# 05_RFFE.net
KiCad netlist of a schematic drawn in Altium Designer
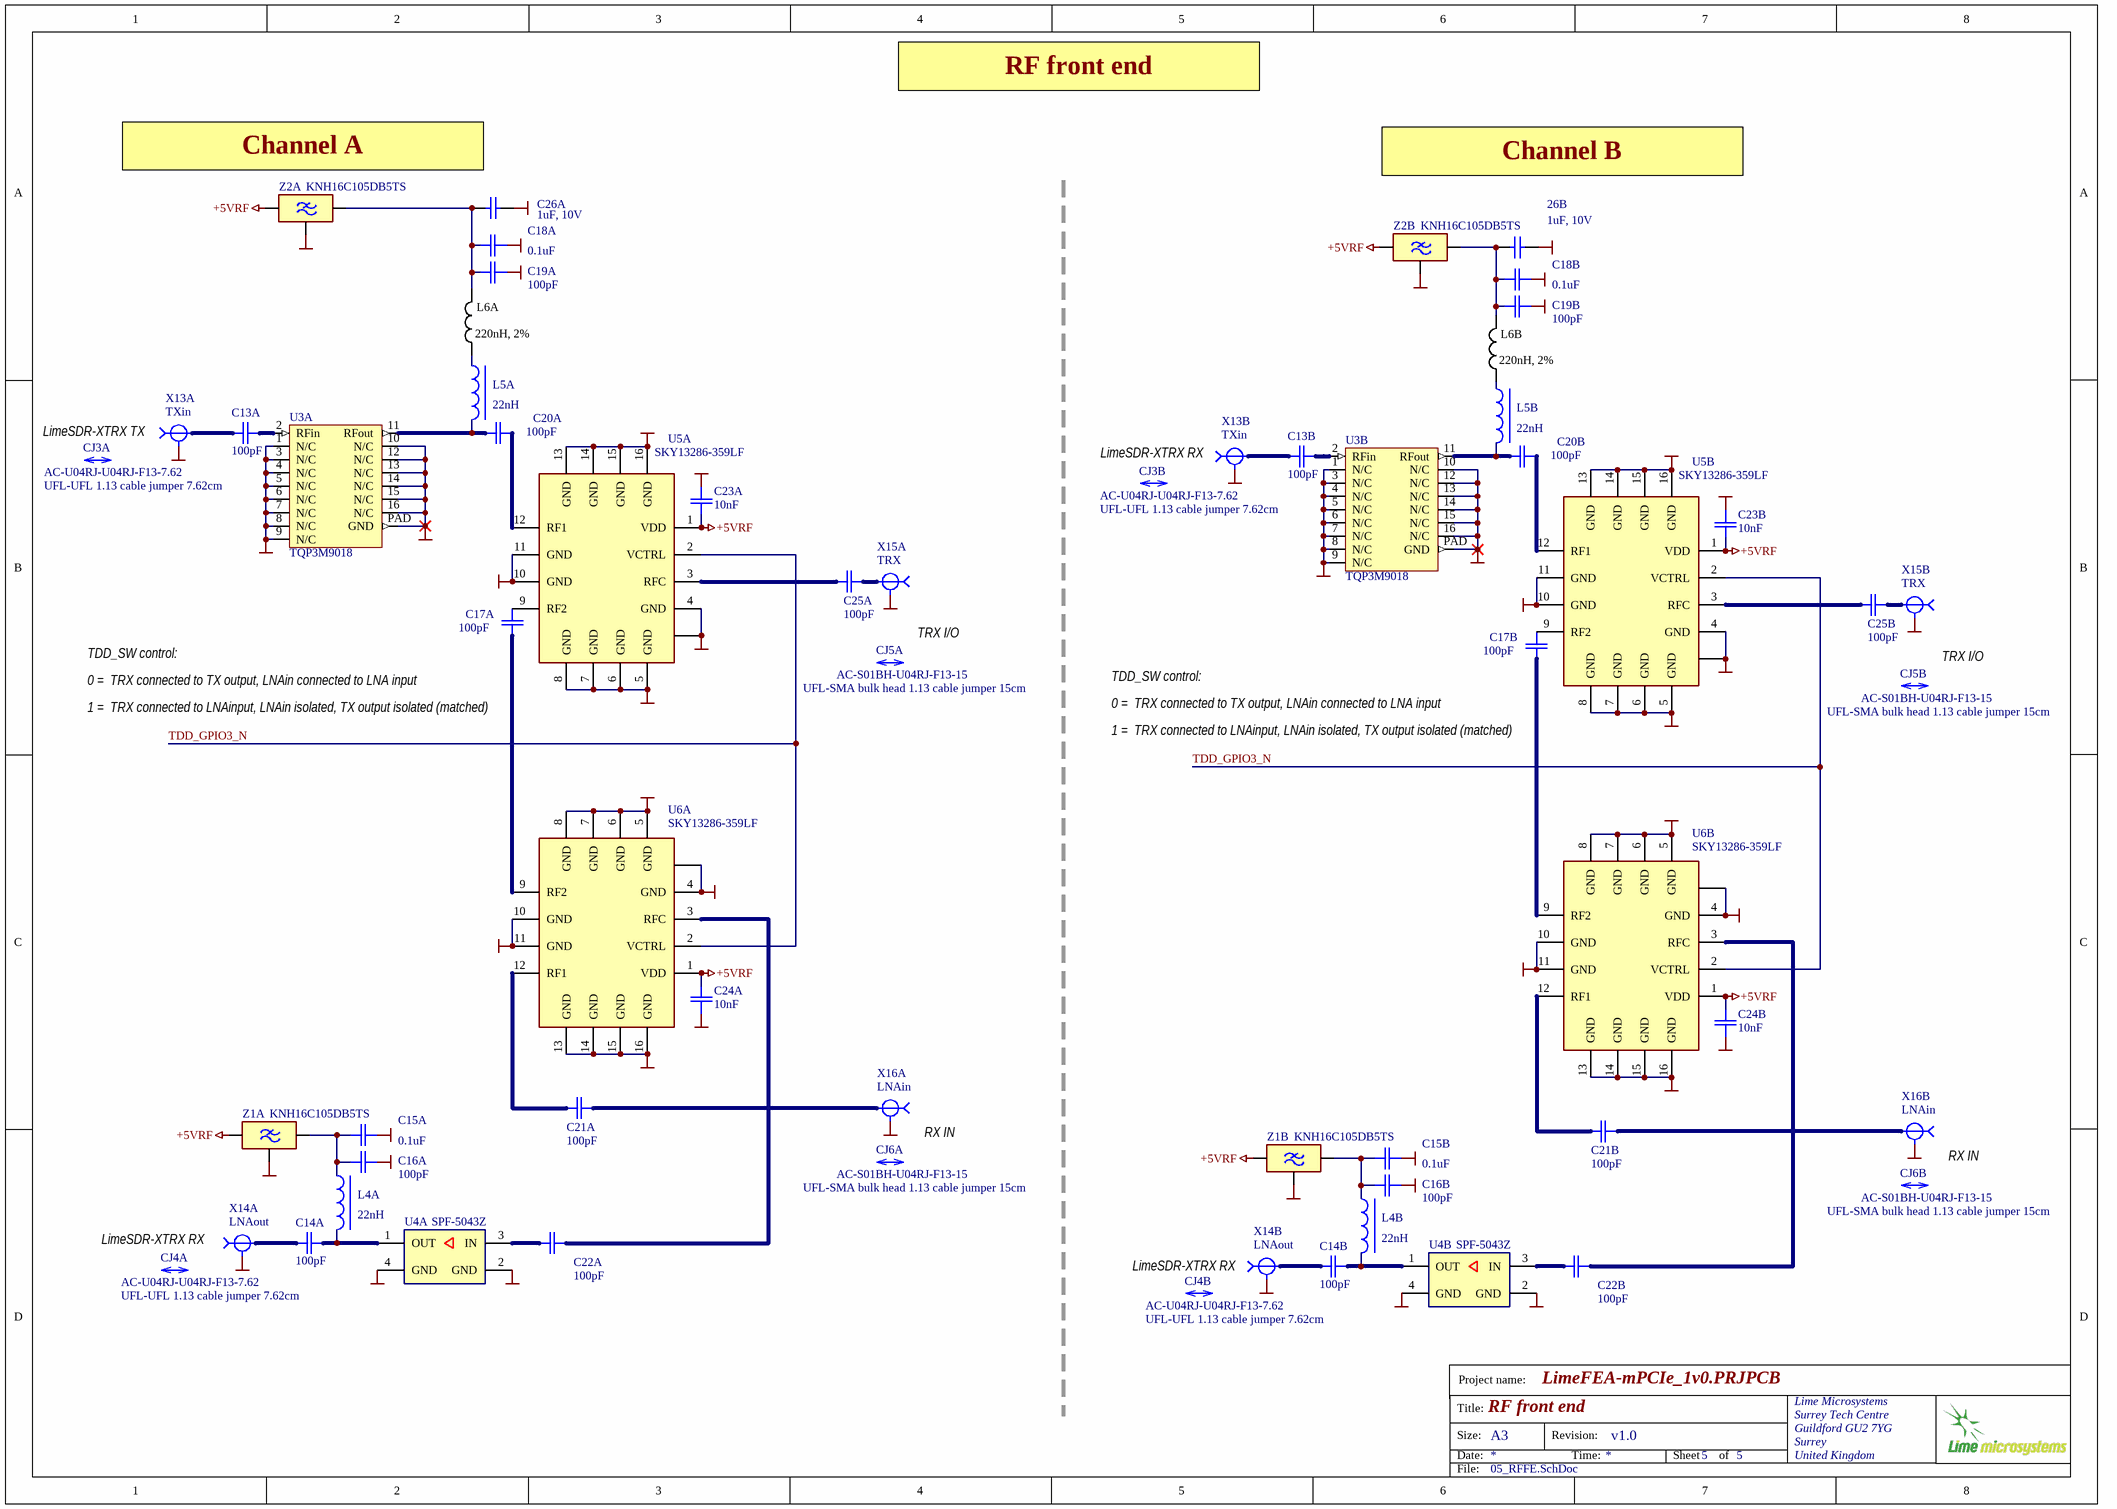
[diagram p0: 05_RFFE.SchDoc]

(export (version "E")
  (design (tool "Eeschema 10.0.6"))
  (components
    (comp (ref "26B")
      (value "1uF, 10V")
      (footprint "CAP0402")
      (description "CAP CER 1UF 10V X5R 0402")
      (fields (field (name "MANUFACTURER") "Yageo") (field (name "TOLERANCE") "±20%"))
      (libsource (lib "LimeMicroAltiumLib_schLib") (part "Cap_0402"))
    )
    (comp (ref "C13A")
      (value "100pF")
      (footprint "C0603-PHILLIPS")
      (description "Capacitor")
      (fields (field (name "MANUFACTURER") "MURATA") (field (name "TOLERANCE") "20%"))
      (libsource (lib "altium-import") (part "root_1_C0603_"))
    )
    (comp (ref "C13B")
      (value "100pF")
      (footprint "C0603-PHILLIPS")
      (description "Capacitor")
      (fields (field (name "MANUFACTURER") "MURATA") (field (name "TOLERANCE") "20%"))
      (libsource (lib "altium-import") (part "root_1_C0603_"))
    )
    (comp (ref "C14A")
      (value "100pF")
      (footprint "C0603-PHILLIPS")
      (description "Capacitor")
      (fields (field (name "MANUFACTURER") "MURATA") (field (name "TOLERANCE") "20%"))
      (libsource (lib "altium-import") (part "root_1_C0603_"))
    )
    (comp (ref "C14B")
      (value "100pF")
      (footprint "C0603-PHILLIPS")
      (description "Capacitor")
      (fields (field (name "MANUFACTURER") "MURATA") (field (name "TOLERANCE") "20%"))
      (libsource (lib "altium-import") (part "root_1_C0603_"))
    )
    (comp (ref "C15A")
      (value "0.1uF")
      (footprint "C0603-PHILLIPS")
      (description "Capacitor")
      (fields (field (name "MANUFACTURER") "MURATA") (field (name "TOLERANCE") "20%"))
      (libsource (lib "altium-import") (part "root_3_mirrored_C0603_"))
    )
    (comp (ref "C15B")
      (value "0.1uF")
      (footprint "C0603-PHILLIPS")
      (description "Capacitor")
      (fields (field (name "MANUFACTURER") "MURATA") (field (name "TOLERANCE") "20%"))
      (libsource (lib "altium-import") (part "root_3_mirrored_C0603_"))
    )
    (comp (ref "C16A")
      (value "100pF")
      (footprint "C0603-PHILLIPS")
      (description "Capacitor")
      (fields (field (name "MANUFACTURER") "MURATA") (field (name "TOLERANCE") "20%"))
      (libsource (lib "altium-import") (part "root_1_C0603_"))
    )
    (comp (ref "C16B")
      (value "100pF")
      (footprint "C0603-PHILLIPS")
      (description "Capacitor")
      (fields (field (name "MANUFACTURER") "MURATA") (field (name "TOLERANCE") "20%"))
      (libsource (lib "altium-import") (part "root_1_C0603_"))
    )
    (comp (ref "C17A")
      (value "100pF")
      (footprint "C0603-PHILLIPS")
      (description "Capacitor")
      (fields (field (name "MANUFACTURER") "MURATA") (field (name "TOLERANCE") "20%"))
      (libsource (lib "altium-import") (part "root_2_C0603_"))
    )
    (comp (ref "C17B")
      (value "100pF")
      (footprint "C0603-PHILLIPS")
      (description "Capacitor")
      (fields (field (name "MANUFACTURER") "MURATA") (field (name "TOLERANCE") "20%"))
      (libsource (lib "altium-import") (part "root_2_C0603_"))
    )
    (comp (ref "C18A")
      (value "0.1uF")
      (footprint "C0603-PHILLIPS")
      (description "Capacitor")
      (fields (field (name "MANUFACTURER") "MURATA") (field (name "TOLERANCE") "20%"))
      (libsource (lib "altium-import") (part "root_3_mirrored_C0603_"))
    )
    (comp (ref "C18B")
      (value "0.1uF")
      (footprint "C0603-PHILLIPS")
      (description "Capacitor")
      (fields (field (name "MANUFACTURER") "MURATA") (field (name "TOLERANCE") "20%"))
      (libsource (lib "altium-import") (part "root_3_mirrored_C0603_"))
    )
    (comp (ref "C19A")
      (value "100pF")
      (footprint "C0603-PHILLIPS")
      (description "Capacitor")
      (fields (field (name "MANUFACTURER") "MURATA") (field (name "TOLERANCE") "20%"))
      (libsource (lib "altium-import") (part "root_1_C0603_"))
    )
    (comp (ref "C19B")
      (value "100pF")
      (footprint "C0603-PHILLIPS")
      (description "Capacitor")
      (fields (field (name "MANUFACTURER") "MURATA") (field (name "TOLERANCE") "20%"))
      (libsource (lib "altium-import") (part "root_1_C0603_"))
    )
    (comp (ref "C20A")
      (value "100pF")
      (footprint "C0603-PHILLIPS")
      (description "Capacitor")
      (fields (field (name "MANUFACTURER") "MURATA") (field (name "TOLERANCE") "20%"))
      (libsource (lib "altium-import") (part "root_1_C0603_"))
    )
    (comp (ref "C20B")
      (value "100pF")
      (footprint "C0603-PHILLIPS")
      (description "Capacitor")
      (fields (field (name "MANUFACTURER") "MURATA") (field (name "TOLERANCE") "20%"))
      (libsource (lib "altium-import") (part "root_1_C0603_"))
    )
    (comp (ref "C21A")
      (value "100pF")
      (footprint "C0603-PHILLIPS")
      (description "Capacitor")
      (fields (field (name "MANUFACTURER") "MURATA") (field (name "TOLERANCE") "20%"))
      (libsource (lib "altium-import") (part "root_1_C0603_"))
    )
    (comp (ref "C21B")
      (value "100pF")
      (footprint "C0603-PHILLIPS")
      (description "Capacitor")
      (fields (field (name "MANUFACTURER") "MURATA") (field (name "TOLERANCE") "20%"))
      (libsource (lib "altium-import") (part "root_1_C0603_"))
    )
    (comp (ref "C22A")
      (value "100pF")
      (footprint "C0603-PHILLIPS")
      (description "Capacitor")
      (fields (field (name "MANUFACTURER") "MURATA") (field (name "TOLERANCE") "20%"))
      (libsource (lib "altium-import") (part "root_1_C0603_"))
    )
    (comp (ref "C22B")
      (value "100pF")
      (footprint "C0603-PHILLIPS")
      (description "Capacitor")
      (fields (field (name "MANUFACTURER") "MURATA") (field (name "TOLERANCE") "20%"))
      (libsource (lib "altium-import") (part "root_1_C0603_"))
    )
    (comp (ref "C23A")
      (value "10nF")
      (footprint "C0603-PHILLIPS")
      (description "Capacitor")
      (fields (field (name "MANUFACTURER") "MURATA") (field (name "TOLERANCE") "20%"))
      (libsource (lib "altium-import") (part "root_2_C0603_"))
    )
    (comp (ref "C23B")
      (value "10nF")
      (footprint "C0603-PHILLIPS")
      (description "Capacitor")
      (fields (field (name "MANUFACTURER") "MURATA") (field (name "TOLERANCE") "20%"))
      (libsource (lib "altium-import") (part "root_2_C0603_"))
    )
    (comp (ref "C24A")
      (value "10nF")
      (footprint "C0603-PHILLIPS")
      (description "Capacitor")
      (fields (field (name "MANUFACTURER") "MURATA") (field (name "TOLERANCE") "20%"))
      (libsource (lib "altium-import") (part "root_0_C0603_"))
    )
    (comp (ref "C24B")
      (value "10nF")
      (footprint "C0603-PHILLIPS")
      (description "Capacitor")
      (fields (field (name "MANUFACTURER") "MURATA") (field (name "TOLERANCE") "20%"))
      (libsource (lib "altium-import") (part "root_0_C0603_"))
    )
    (comp (ref "C25A")
      (value "100pF")
      (footprint "C0603-PHILLIPS")
      (description "Capacitor")
      (fields (field (name "MANUFACTURER") "MURATA") (field (name "TOLERANCE") "20%"))
      (libsource (lib "altium-import") (part "root_1_C0603_"))
    )
    (comp (ref "C25B")
      (value "100pF")
      (footprint "C0603-PHILLIPS")
      (description "Capacitor")
      (fields (field (name "MANUFACTURER") "MURATA") (field (name "TOLERANCE") "20%"))
      (libsource (lib "altium-import") (part "root_1_C0603_"))
    )
    (comp (ref "C26A")
      (value "1uF, 10V")
      (footprint "CAP0402")
      (description "CAP CER 1UF 10V X5R 0402")
      (fields (field (name "MANUFACTURER") "Yageo") (field (name "TOLERANCE") "±20%"))
      (libsource (lib "LimeMicroAltiumLib_schLib") (part "Cap_0402"))
    )
    (comp (ref "CJ3A")
      (value "AC-U04RJ-U04RJ-F13-7.62")
      (description "Cable jumper")
      (fields
        (field (name "MANUFACTURER") "RFSupplier")
        (field (name "MISC") "UFL-UFL 1.13 cable jumper 7.62cm")
      )
      (libsource (lib "LimeFEA-mPCIe_1v0") (part "Mating part"))
    )
    (comp (ref "CJ3B")
      (value "AC-U04RJ-U04RJ-F13-7.62")
      (description "Cable jumper")
      (fields
        (field (name "MANUFACTURER") "RFSupplier")
        (field (name "MISC") "UFL-UFL 1.13 cable jumper 7.62cm")
      )
      (libsource (lib "Andy") (part "Mating part"))
    )
    (comp (ref "CJ4A")
      (value "AC-U04RJ-U04RJ-F13-7.62")
      (description "Cable jumper")
      (fields
        (field (name "MANUFACTURER") "RFSupplier")
        (field (name "MISC") "UFL-UFL 1.13 cable jumper 7.62cm")
      )
      (libsource (lib "LimeFEA-mPCIe_1v0") (part "Mating part"))
    )
    (comp (ref "CJ4B")
      (value "AC-U04RJ-U04RJ-F13-7.62")
      (description "Cable jumper")
      (fields
        (field (name "MANUFACTURER") "RFSupplier")
        (field (name "MISC") "UFL-UFL 1.13 cable jumper 7.62cm")
      )
      (libsource (lib "LimeFEA-mPCIe_1v0") (part "Mating part"))
    )
    (comp (ref "CJ5A")
      (value "AC-S01BH-U04RJ-F13-15")
      (description "Cable jumper")
      (fields
        (field (name "MANUFACTURER") "RFSupplier")
        (field (name "MISC") "UFL-SMA bulk head 1.13 cable jumper 15cm")
      )
      (libsource (lib "Andy") (part "Mating part"))
    )
    (comp (ref "CJ5B")
      (value "AC-S01BH-U04RJ-F13-15")
      (description "Cable jumper")
      (fields
        (field (name "MANUFACTURER") "RFSupplier")
        (field (name "MISC") "UFL-SMA bulk head 1.13 cable jumper 15cm")
      )
      (libsource (lib "LimeFEA-mPCIe_1v0") (part "Mating part"))
    )
    (comp (ref "CJ6A")
      (value "AC-S01BH-U04RJ-F13-15")
      (description "Cable jumper")
      (fields
        (field (name "MANUFACTURER") "RFSupplier")
        (field (name "MISC") "UFL-SMA bulk head 1.13 cable jumper 15cm")
      )
      (libsource (lib "Andy") (part "Mating part"))
    )
    (comp (ref "CJ6B")
      (value "AC-S01BH-U04RJ-F13-15")
      (description "Cable jumper")
      (fields
        (field (name "MANUFACTURER") "RFSupplier")
        (field (name "MISC") "UFL-SMA bulk head 1.13 cable jumper 15cm")
      )
      (libsource (lib "LimeFEA-mPCIe_1v0") (part "Mating part"))
    )
    (comp (ref "L4A")
      (value "22nH")
      (footprint "TF160808-Phillips")
      (description "Coil")
      (fields (field (name "MANUFACTURER") "MuRata"))
      (libsource (lib "LimeFEA-mPCIe_1v0") (part "TF160808"))
    )
    (comp (ref "L4B")
      (value "22nH")
      (footprint "TF160808-Phillips")
      (description "Coil")
      (fields (field (name "MANUFACTURER") "MuRata"))
      (libsource (lib "LimeFEA-mPCIe_1v0") (part "TF160808"))
    )
    (comp (ref "L5A")
      (value "22nH")
      (footprint "TF160808-Phillips")
      (description "Coil")
      (fields (field (name "MANUFACTURER") "MuRata"))
      (libsource (lib "LimeFEA-mPCIe_1v0") (part "TF160808"))
    )
    (comp (ref "L5B")
      (value "22nH")
      (footprint "TF160808-Phillips")
      (description "Coil")
      (fields (field (name "MANUFACTURER") "MuRata"))
      (libsource (lib "LimeFEA-mPCIe_1v0") (part "TF160808"))
    )
    (comp (ref "L6A")
      (value "220nH, 2%")
      (footprint "RES0603")
      (description "Power Inductors - SMD .22 UH 20%")
      (fields (field (name "MANUFACTURER") "TDK"))
      (libsource (lib "LimeMicroAltiumLib_schLib") (part "Inductor"))
    )
    (comp (ref "L6B")
      (value "220nH, 2%")
      (footprint "RES0603")
      (description "Power Inductors - SMD .22 UH 20%")
      (fields (field (name "MANUFACTURER") "TDK"))
      (libsource (lib "LimeMicroAltiumLib_schLib") (part "Inductor"))
    )
    (comp (ref "U3A")
      (value "TQP3M9018")
      (footprint "TQP3M9018_PA_QFN16")
      (description "RF Amplifier .05-4GHz P1dB= 22dB Gain 26.4dB 5Volts")
      (fields (field (name "MANUFACTURER") "Qorvo"))
      (libsource (lib "LimeMicroAltiumLib") (part "TQP3M9018_PA"))
    )
    (comp (ref "U3B")
      (value "TQP3M9018")
      (footprint "TQP3M9018_PA_QFN16")
      (description "RF Amplifier .05-4GHz P1dB= 22dB Gain 26.4dB 5Volts")
      (fields (field (name "MANUFACTURER") "Qorvo"))
      (libsource (lib "LimeMicroAltiumLib") (part "TQP3M9018_PA"))
    )
    (comp (ref "U4A")
      (value "SPF-5043Z")
      (footprint "SOT-343[2X1.25]")
      (description "IC")
      (fields (field (name "MANUFACTURER") "RFMD"))
      (libsource (lib "LimeFEA-mPCIe_1v0") (part "SPF-5043Z"))
    )
    (comp (ref "U4B")
      (value "SPF-5043Z")
      (footprint "SOT-343[2X1.25]")
      (description "IC")
      (fields (field (name "MANUFACTURER") "RFMD"))
      (libsource (lib "LimeFEA-mPCIe_1v0") (part "SPF-5043Z"))
    )
    (comp (ref "U5A")
      (value "SKY13286-359LF")
      (footprint "QFN16(4x4/0.65mm) SQ")
      (description "IC RF SPDT Absorptive Switch")
      (fields (field (name "MANUFACTURER") "Skyworks"))
      (libsource (lib "LimeFEA-mPCIe_1v0") (part "SKY13286-359LF"))
    )
    (comp (ref "U5B")
      (value "SKY13286-359LF")
      (footprint "QFN16(4x4/0.65mm) SQ")
      (description "IC RF SPDT Absorptive Switch")
      (fields (field (name "MANUFACTURER") "Skyworks"))
      (libsource (lib "LimeFEA-mPCIe_1v0") (part "SKY13286-359LF"))
    )
    (comp (ref "U6A")
      (value "SKY13286-359LF")
      (footprint "QFN16(4x4/0.65mm) SQ")
      (description "IC RF SPDT Absorptive Switch")
      (fields (field (name "MANUFACTURER") "Skyworks"))
      (libsource (lib "") (part "SKY13286-359LF_1"))
    )
    (comp (ref "U6B")
      (value "SKY13286-359LF")
      (footprint "QFN16(4x4/0.65mm) SQ")
      (description "IC RF SPDT Absorptive Switch")
      (fields (field (name "MANUFACTURER") "Skyworks"))
      (libsource (lib "") (part "SKY13286-359LF_1"))
    )
    (comp (ref "X13A")
      (value "0734120110")
      (footprint "U_FL")
      (description "Connector (UMCC)")
      (fields (field (name "MANUFACTURER") "Molex") (field (name "MISC") "TXin"))
      (libsource (lib "LimeFEA-mPCIe_1v0") (part "U_FL"))
    )
    (comp (ref "X13B")
      (value "0734120110")
      (footprint "U_FL")
      (description "Connector (UMCC)")
      (fields (field (name "MANUFACTURER") "Molex") (field (name "MISC") "TXin"))
      (libsource (lib "LimeFEA-mPCIe_1v0") (part "U_FL"))
    )
    (comp (ref "X14A")
      (value "0734120110")
      (footprint "U_FL")
      (description "Connector (UMCC)")
      (fields (field (name "MANUFACTURER") "Molex") (field (name "MISC") "LNAout"))
      (libsource (lib "LimeFEA-mPCIe_1v0") (part "U_FL"))
    )
    (comp (ref "X14B")
      (value "0734120110")
      (footprint "U_FL")
      (description "Connector (UMCC)")
      (fields (field (name "MANUFACTURER") "Molex") (field (name "MISC") "LNAout"))
      (libsource (lib "LimeFEA-mPCIe_1v0") (part "U_FL"))
    )
    (comp (ref "X15A")
      (value "0734120110")
      (footprint "U_FL")
      (description "Connector (UMCC)")
      (fields (field (name "MANUFACTURER") "Molex") (field (name "MISC") "TRX"))
      (libsource (lib "LimeFEA-mPCIe_1v0") (part "U_FL"))
    )
    (comp (ref "X15B")
      (value "0734120110")
      (footprint "U_FL")
      (description "Connector (UMCC)")
      (fields (field (name "MANUFACTURER") "Molex") (field (name "MISC") "TRX"))
      (libsource (lib "LimeFEA-mPCIe_1v0") (part "U_FL"))
    )
    (comp (ref "X16A")
      (value "0734120110")
      (footprint "U_FL")
      (description "Connector (UMCC)")
      (fields (field (name "MANUFACTURER") "Molex") (field (name "MISC") "LNAin"))
      (libsource (lib "LimeFEA-mPCIe_1v0") (part "U_FL"))
    )
    (comp (ref "X16B")
      (value "0734120110")
      (footprint "U_FL")
      (description "Connector (UMCC)")
      (fields (field (name "MANUFACTURER") "Molex") (field (name "MISC") "LNAin"))
      (libsource (lib "LimeFEA-mPCIe_1v0") (part "U_FL"))
    )
    (comp (ref "Z1A")
      (value "KNH16C105DB5TS")
      (footprint "KNH16 - DB Serie")
      (description "EMI Filter")
      (fields (field (name "MANUFACTURER") "AVX / Kyocera"))
      (libsource (lib "LimeFEA-mPCIe_1v0") (part "KNH16 Serie"))
    )
    (comp (ref "Z1B")
      (value "KNH16C105DB5TS")
      (footprint "KNH16 - DB Serie")
      (description "EMI Filter")
      (fields (field (name "MANUFACTURER") "AVX / Kyocera"))
      (libsource (lib "LimeFEA-mPCIe_1v0") (part "KNH16 Serie"))
    )
    (comp (ref "Z2A")
      (value "KNH16C105DB5TS")
      (footprint "KNH16 - DB Serie")
      (description "EMI Filter")
      (fields (field (name "MANUFACTURER") "AVX / Kyocera"))
      (libsource (lib "LimeFEA-mPCIe_1v0") (part "KNH16 Serie"))
    )
    (comp (ref "Z2B")
      (value "KNH16C105DB5TS")
      (footprint "KNH16 - DB Serie")
      (description "EMI Filter")
      (fields (field (name "MANUFACTURER") "AVX / Kyocera"))
      (libsource (lib "LimeFEA-mPCIe_1v0") (part "KNH16 Serie"))
    )
  )
  (nets
    (net (code "1") (name "+5VRF") (class "Default")
      (node (ref "C23A") (pin "1") (pinfunction "1_1") (pintype "passive"))
      (node (ref "C23B") (pin "1") (pinfunction "1_1") (pintype "passive"))
      (node (ref "C24A") (pin "1") (pinfunction "1_1") (pintype "passive"))
      (node (ref "C24B") (pin "1") (pinfunction "1_1") (pintype "passive"))
      (node (ref "U5A") (pin "1") (pinfunction "VDD_1") (pintype "passive"))
      (node (ref "U5B") (pin "1") (pinfunction "VDD_1") (pintype "passive"))
      (node (ref "U6A") (pin "1") (pinfunction "VDD_1") (pintype "passive"))
      (node (ref "U6B") (pin "1") (pinfunction "VDD_1") (pintype "passive"))
      (node (ref "Z1A") (pin "1") (pinfunction "1_1") (pintype "passive"))
      (node (ref "Z1B") (pin "1") (pinfunction "1_1") (pintype "passive"))
      (node (ref "Z2A") (pin "1") (pinfunction "1_1") (pintype "passive"))
      (node (ref "Z2B") (pin "1") (pinfunction "1_1") (pintype "passive"))
    )
    (net (code "2") (name "/TDD_GPIO3_N") (class "Default")
      (node (ref "U5A") (pin "2") (pinfunction "VCTRL_2") (pintype "passive"))
      (node (ref "U5B") (pin "2") (pinfunction "VCTRL_2") (pintype "passive"))
      (node (ref "U6A") (pin "2") (pinfunction "VCTRL_2") (pintype "passive"))
      (node (ref "U6B") (pin "2") (pinfunction "VCTRL_2") (pintype "passive"))
    )
    (net (code "3") (name "GND") (class "Default")
      (node (ref "26B") (pin "1") (pinfunction "1_1") (pintype "passive"))
      (node (ref "C15A") (pin "2") (pinfunction "2_2") (pintype "passive"))
      (node (ref "C15B") (pin "2") (pinfunction "2_2") (pintype "passive"))
      (node (ref "C16A") (pin "2") (pinfunction "2_2") (pintype "passive"))
      (node (ref "C16B") (pin "2") (pinfunction "2_2") (pintype "passive"))
      (node (ref "C18A") (pin "2") (pinfunction "2_2") (pintype "passive"))
      (node (ref "C18B") (pin "2") (pinfunction "2_2") (pintype "passive"))
      (node (ref "C19A") (pin "2") (pinfunction "2_2") (pintype "passive"))
      (node (ref "C19B") (pin "2") (pinfunction "2_2") (pintype "passive"))
      (node (ref "C23A") (pin "2") (pinfunction "2_2") (pintype "passive"))
      (node (ref "C23B") (pin "2") (pinfunction "2_2") (pintype "passive"))
      (node (ref "C24A") (pin "2") (pinfunction "2_2") (pintype "passive"))
      (node (ref "C24B") (pin "2") (pinfunction "2_2") (pintype "passive"))
      (node (ref "C26A") (pin "1") (pinfunction "1_1") (pintype "passive"))
      (node (ref "U3A") (pin "1") (pinfunction "N/C_1") (pintype "passive"))
      (node (ref "U3A") (pin "10") (pinfunction "N/C_10") (pintype "passive"))
      (node (ref "U3A") (pin "12") (pinfunction "N/C_12") (pintype "passive"))
      (node (ref "U3A") (pin "13") (pinfunction "N/C_13") (pintype "passive"))
      (node (ref "U3A") (pin "14") (pinfunction "N/C_14") (pintype "passive"))
      (node (ref "U3A") (pin "15") (pinfunction "N/C_15") (pintype "passive"))
      (node (ref "U3A") (pin "16") (pinfunction "N/C_16") (pintype "passive"))
      (node (ref "U3A") (pin "3") (pinfunction "N/C_3") (pintype "passive"))
      (node (ref "U3A") (pin "4") (pinfunction "N/C_4") (pintype "passive"))
      (node (ref "U3A") (pin "5") (pinfunction "N/C_5") (pintype "passive"))
      (node (ref "U3A") (pin "6") (pinfunction "N/C_6") (pintype "passive"))
      (node (ref "U3A") (pin "7") (pinfunction "N/C_7") (pintype "passive"))
      (node (ref "U3A") (pin "8") (pinfunction "N/C_8") (pintype "passive"))
      (node (ref "U3A") (pin "9") (pinfunction "N/C_9") (pintype "passive"))
      (node (ref "U3A") (pin "PAD") (pinfunction "GND_PAD") (pintype "output"))
      (node (ref "U3B") (pin "1") (pinfunction "N/C_1") (pintype "passive"))
      (node (ref "U3B") (pin "10") (pinfunction "N/C_10") (pintype "passive"))
      (node (ref "U3B") (pin "12") (pinfunction "N/C_12") (pintype "passive"))
      (node (ref "U3B") (pin "13") (pinfunction "N/C_13") (pintype "passive"))
      (node (ref "U3B") (pin "14") (pinfunction "N/C_14") (pintype "passive"))
      (node (ref "U3B") (pin "15") (pinfunction "N/C_15") (pintype "passive"))
      (node (ref "U3B") (pin "16") (pinfunction "N/C_16") (pintype "passive"))
      (node (ref "U3B") (pin "3") (pinfunction "N/C_3") (pintype "passive"))
      (node (ref "U3B") (pin "4") (pinfunction "N/C_4") (pintype "passive"))
      (node (ref "U3B") (pin "5") (pinfunction "N/C_5") (pintype "passive"))
      (node (ref "U3B") (pin "6") (pinfunction "N/C_6") (pintype "passive"))
      (node (ref "U3B") (pin "7") (pinfunction "N/C_7") (pintype "passive"))
      (node (ref "U3B") (pin "8") (pinfunction "N/C_8") (pintype "passive"))
      (node (ref "U3B") (pin "9") (pinfunction "N/C_9") (pintype "passive"))
      (node (ref "U3B") (pin "PAD") (pinfunction "GND_PAD") (pintype "output"))
      (node (ref "U4A") (pin "2") (pinfunction "GND_2") (pintype "power_in"))
      (node (ref "U4A") (pin "4") (pinfunction "GND_4") (pintype "power_in"))
      (node (ref "U4B") (pin "2") (pinfunction "GND_2") (pintype "power_in"))
      (node (ref "U4B") (pin "4") (pinfunction "GND_4") (pintype "power_in"))
      (node (ref "U5A") (pin "0") (pinfunction "PAD_0") (pintype "passive"))
      (node (ref "U5A") (pin "10") (pinfunction "GND_10") (pintype "passive"))
      (node (ref "U5A") (pin "11") (pinfunction "GND_11") (pintype "passive"))
      (node (ref "U5A") (pin "13") (pinfunction "GND_13") (pintype "passive"))
      (node (ref "U5A") (pin "14") (pinfunction "GND_14") (pintype "passive"))
      (node (ref "U5A") (pin "15") (pinfunction "GND_15") (pintype "passive"))
      (node (ref "U5A") (pin "16") (pinfunction "GND_16") (pintype "passive"))
      (node (ref "U5A") (pin "4") (pinfunction "GND_4") (pintype "passive"))
      (node (ref "U5A") (pin "5") (pinfunction "GND_5") (pintype "passive"))
      (node (ref "U5A") (pin "6") (pinfunction "GND_6") (pintype "passive"))
      (node (ref "U5A") (pin "7") (pinfunction "GND_7") (pintype "passive"))
      (node (ref "U5A") (pin "8") (pinfunction "GND_8") (pintype "passive"))
      (node (ref "U5B") (pin "0") (pinfunction "PAD_0") (pintype "passive"))
      (node (ref "U5B") (pin "10") (pinfunction "GND_10") (pintype "passive"))
      (node (ref "U5B") (pin "11") (pinfunction "GND_11") (pintype "passive"))
      (node (ref "U5B") (pin "13") (pinfunction "GND_13") (pintype "passive"))
      (node (ref "U5B") (pin "14") (pinfunction "GND_14") (pintype "passive"))
      (node (ref "U5B") (pin "15") (pinfunction "GND_15") (pintype "passive"))
      (node (ref "U5B") (pin "16") (pinfunction "GND_16") (pintype "passive"))
      (node (ref "U5B") (pin "4") (pinfunction "GND_4") (pintype "passive"))
      (node (ref "U5B") (pin "5") (pinfunction "GND_5") (pintype "passive"))
      (node (ref "U5B") (pin "6") (pinfunction "GND_6") (pintype "passive"))
      (node (ref "U5B") (pin "7") (pinfunction "GND_7") (pintype "passive"))
      (node (ref "U5B") (pin "8") (pinfunction "GND_8") (pintype "passive"))
      (node (ref "U6A") (pin "0") (pinfunction "PAD_0") (pintype "passive"))
      (node (ref "U6A") (pin "10") (pinfunction "GND_10") (pintype "passive"))
      (node (ref "U6A") (pin "11") (pinfunction "GND_11") (pintype "passive"))
      (node (ref "U6A") (pin "13") (pinfunction "GND_13") (pintype "passive"))
      (node (ref "U6A") (pin "14") (pinfunction "GND_14") (pintype "passive"))
      (node (ref "U6A") (pin "15") (pinfunction "GND_15") (pintype "passive"))
      (node (ref "U6A") (pin "16") (pinfunction "GND_16") (pintype "passive"))
      (node (ref "U6A") (pin "4") (pinfunction "GND_4") (pintype "passive"))
      (node (ref "U6A") (pin "5") (pinfunction "GND_5") (pintype "passive"))
      (node (ref "U6A") (pin "6") (pinfunction "GND_6") (pintype "passive"))
      (node (ref "U6A") (pin "7") (pinfunction "GND_7") (pintype "passive"))
      (node (ref "U6A") (pin "8") (pinfunction "GND_8") (pintype "passive"))
      (node (ref "U6B") (pin "0") (pinfunction "PAD_0") (pintype "passive"))
      (node (ref "U6B") (pin "10") (pinfunction "GND_10") (pintype "passive"))
      (node (ref "U6B") (pin "11") (pinfunction "GND_11") (pintype "passive"))
      (node (ref "U6B") (pin "13") (pinfunction "GND_13") (pintype "passive"))
      (node (ref "U6B") (pin "14") (pinfunction "GND_14") (pintype "passive"))
      (node (ref "U6B") (pin "15") (pinfunction "GND_15") (pintype "passive"))
      (node (ref "U6B") (pin "16") (pinfunction "GND_16") (pintype "passive"))
      (node (ref "U6B") (pin "4") (pinfunction "GND_4") (pintype "passive"))
      (node (ref "U6B") (pin "5") (pinfunction "GND_5") (pintype "passive"))
      (node (ref "U6B") (pin "6") (pinfunction "GND_6") (pintype "passive"))
      (node (ref "U6B") (pin "7") (pinfunction "GND_7") (pintype "passive"))
      (node (ref "U6B") (pin "8") (pinfunction "GND_8") (pintype "passive"))
      (node (ref "X13A") (pin "2") (pinfunction "GND_2") (pintype "passive"))
      (node (ref "X13B") (pin "2") (pinfunction "GND_2") (pintype "passive"))
      (node (ref "X14A") (pin "2") (pinfunction "GND_2") (pintype "passive"))
      (node (ref "X14B") (pin "2") (pinfunction "GND_2") (pintype "passive"))
      (node (ref "X15A") (pin "2") (pinfunction "GND_2") (pintype "passive"))
      (node (ref "X15B") (pin "2") (pinfunction "GND_2") (pintype "passive"))
      (node (ref "X16A") (pin "2") (pinfunction "GND_2") (pintype "passive"))
      (node (ref "X16B") (pin "2") (pinfunction "GND_2") (pintype "passive"))
      (node (ref "Z1A") (pin "2") (pinfunction "2_2") (pintype "passive"))
      (node (ref "Z1B") (pin "2") (pinfunction "2_2") (pintype "passive"))
      (node (ref "Z2A") (pin "2") (pinfunction "2_2") (pintype "passive"))
      (node (ref "Z2B") (pin "2") (pinfunction "2_2") (pintype "passive"))
    )
    (net (code "4") (name "Net-(26B-Pad2)") (class "Default")
      (node (ref "26B") (pin "2") (pinfunction "2_2") (pintype "passive"))
      (node (ref "C18B") (pin "1") (pinfunction "1_1") (pintype "passive"))
      (node (ref "C19B") (pin "1") (pinfunction "1_1") (pintype "passive"))
      (node (ref "L6B") (pin "1") (pinfunction "1_1") (pintype "passive"))
      (node (ref "Z2B") (pin "3") (pinfunction "3_3") (pintype "passive"))
    )
    (net (code "5") (name "Net-(C13A-Pad1)") (class "Default")
      (node (ref "C13A") (pin "1") (pinfunction "1_1") (pintype "passive"))
      (node (ref "X13A") (pin "1") (pinfunction "1_1") (pintype "passive"))
    )
    (net (code "6") (name "Net-(C13B-Pad1)") (class "Default")
      (node (ref "C13B") (pin "1") (pinfunction "1_1") (pintype "passive"))
      (node (ref "X13B") (pin "1") (pinfunction "1_1") (pintype "passive"))
    )
    (net (code "7") (name "Net-(C14A-Pad1)") (class "Default")
      (node (ref "C14A") (pin "1") (pinfunction "1_1") (pintype "passive"))
      (node (ref "X14A") (pin "1") (pinfunction "1_1") (pintype "passive"))
    )
    (net (code "8") (name "Net-(C14B-Pad1)") (class "Default")
      (node (ref "C14B") (pin "1") (pinfunction "1_1") (pintype "passive"))
      (node (ref "X14B") (pin "1") (pinfunction "1_1") (pintype "passive"))
    )
    (net (code "9") (name "Net-(C15A-Pad1)") (class "Default")
      (node (ref "C15A") (pin "1") (pinfunction "1_1") (pintype "passive"))
      (node (ref "C16A") (pin "1") (pinfunction "1_1") (pintype "passive"))
      (node (ref "L4A") (pin "1") (pinfunction "1_1") (pintype "passive"))
      (node (ref "Z1A") (pin "3") (pinfunction "3_3") (pintype "passive"))
    )
    (net (code "10") (name "Net-(C15B-Pad1)") (class "Default")
      (node (ref "C15B") (pin "1") (pinfunction "1_1") (pintype "passive"))
      (node (ref "C16B") (pin "1") (pinfunction "1_1") (pintype "passive"))
      (node (ref "L4B") (pin "1") (pinfunction "1_1") (pintype "passive"))
      (node (ref "Z1B") (pin "3") (pinfunction "3_3") (pintype "passive"))
    )
    (net (code "11") (name "Net-(C18A-Pad1)") (class "Default")
      (node (ref "C18A") (pin "1") (pinfunction "1_1") (pintype "passive"))
      (node (ref "C19A") (pin "1") (pinfunction "1_1") (pintype "passive"))
      (node (ref "C26A") (pin "2") (pinfunction "2_2") (pintype "passive"))
      (node (ref "L6A") (pin "1") (pinfunction "1_1") (pintype "passive"))
      (node (ref "Z2A") (pin "3") (pinfunction "3_3") (pintype "passive"))
    )
    (net (code "12") (name "Net-(C21A-Pad2)") (class "Default")
      (node (ref "C21A") (pin "2") (pinfunction "2_2") (pintype "passive"))
      (node (ref "X16A") (pin "1") (pinfunction "1_1") (pintype "passive"))
    )
    (net (code "13") (name "Net-(C21B-Pad2)") (class "Default")
      (node (ref "C21B") (pin "2") (pinfunction "2_2") (pintype "passive"))
      (node (ref "X16B") (pin "1") (pinfunction "1_1") (pintype "passive"))
    )
    (net (code "14") (name "Net-(C25A-Pad2)") (class "Default")
      (node (ref "C25A") (pin "2") (pinfunction "2_2") (pintype "passive"))
      (node (ref "X15A") (pin "1") (pinfunction "1_1") (pintype "passive"))
    )
    (net (code "15") (name "Net-(C25B-Pad2)") (class "Default")
      (node (ref "C25B") (pin "2") (pinfunction "2_2") (pintype "passive"))
      (node (ref "X15B") (pin "1") (pinfunction "1_1") (pintype "passive"))
    )
    (net (code "16") (name "Net-(L5A-Pad1)") (class "Default")
      (node (ref "L5A") (pin "1") (pinfunction "1_1") (pintype "passive"))
      (node (ref "L6A") (pin "2") (pinfunction "2_2") (pintype "passive"))
    )
    (net (code "17") (name "Net-(L5B-Pad1)") (class "Default")
      (node (ref "L5B") (pin "1") (pinfunction "1_1") (pintype "passive"))
      (node (ref "L6B") (pin "2") (pinfunction "2_2") (pintype "passive"))
    )
    (net (code "18") (name "Net-(U3A-RFin)") (class "Default")
      (node (ref "C13A") (pin "2") (pinfunction "2_2") (pintype "passive"))
      (node (ref "U3A") (pin "2") (pinfunction "RFin_2") (pintype "input"))
    )
    (net (code "19") (name "Net-(U3A-RFout)") (class "Default")
      (node (ref "C20A") (pin "1") (pinfunction "1_1") (pintype "passive"))
      (node (ref "L5A") (pin "2") (pinfunction "2_2") (pintype "passive"))
      (node (ref "U3A") (pin "11") (pinfunction "RFout_11") (pintype "output"))
    )
    (net (code "20") (name "Net-(U3B-RFin)") (class "Default")
      (node (ref "C13B") (pin "2") (pinfunction "2_2") (pintype "passive"))
      (node (ref "U3B") (pin "2") (pinfunction "RFin_2") (pintype "input"))
    )
    (net (code "21") (name "Net-(U3B-RFout)") (class "Default")
      (node (ref "C20B") (pin "1") (pinfunction "1_1") (pintype "passive"))
      (node (ref "L5B") (pin "2") (pinfunction "2_2") (pintype "passive"))
      (node (ref "U3B") (pin "11") (pinfunction "RFout_11") (pintype "output"))
    )
    (net (code "22") (name "Net-(U4A-IN)") (class "Default")
      (node (ref "C22A") (pin "1") (pinfunction "1_1") (pintype "passive"))
      (node (ref "U4A") (pin "3") (pinfunction "IN_3") (pintype "passive"))
    )
    (net (code "23") (name "Net-(U4A-OUT)") (class "Default")
      (node (ref "C14A") (pin "2") (pinfunction "2_2") (pintype "passive"))
      (node (ref "L4A") (pin "2") (pinfunction "2_2") (pintype "passive"))
      (node (ref "U4A") (pin "1") (pinfunction "OUT_1") (pintype "passive"))
    )
    (net (code "24") (name "Net-(U4B-IN)") (class "Default")
      (node (ref "C22B") (pin "1") (pinfunction "1_1") (pintype "passive"))
      (node (ref "U4B") (pin "3") (pinfunction "IN_3") (pintype "passive"))
    )
    (net (code "25") (name "Net-(U4B-OUT)") (class "Default")
      (node (ref "C14B") (pin "2") (pinfunction "2_2") (pintype "passive"))
      (node (ref "L4B") (pin "2") (pinfunction "2_2") (pintype "passive"))
      (node (ref "U4B") (pin "1") (pinfunction "OUT_1") (pintype "passive"))
    )
    (net (code "26") (name "Net-(U5A-RF1)") (class "Default")
      (node (ref "C20A") (pin "2") (pinfunction "2_2") (pintype "passive"))
      (node (ref "U5A") (pin "12") (pinfunction "RF1_12") (pintype "passive"))
    )
    (net (code "27") (name "Net-(U5A-RF2)") (class "Default")
      (node (ref "C17A") (pin "2") (pinfunction "2_2") (pintype "passive"))
      (node (ref "U5A") (pin "9") (pinfunction "RF2_9") (pintype "passive"))
    )
    (net (code "28") (name "Net-(U5A-RFC)") (class "Default")
      (node (ref "C25A") (pin "1") (pinfunction "1_1") (pintype "passive"))
      (node (ref "U5A") (pin "3") (pinfunction "RFC_3") (pintype "passive"))
    )
    (net (code "29") (name "Net-(U5B-RF1)") (class "Default")
      (node (ref "C20B") (pin "2") (pinfunction "2_2") (pintype "passive"))
      (node (ref "U5B") (pin "12") (pinfunction "RF1_12") (pintype "passive"))
    )
    (net (code "30") (name "Net-(U5B-RF2)") (class "Default")
      (node (ref "C17B") (pin "2") (pinfunction "2_2") (pintype "passive"))
      (node (ref "U5B") (pin "9") (pinfunction "RF2_9") (pintype "passive"))
    )
    (net (code "31") (name "Net-(U5B-RFC)") (class "Default")
      (node (ref "C25B") (pin "1") (pinfunction "1_1") (pintype "passive"))
      (node (ref "U5B") (pin "3") (pinfunction "RFC_3") (pintype "passive"))
    )
    (net (code "32") (name "Net-(U6A-RF1)") (class "Default")
      (node (ref "C21A") (pin "1") (pinfunction "1_1") (pintype "passive"))
      (node (ref "U6A") (pin "12") (pinfunction "RF1_12") (pintype "passive"))
    )
    (net (code "33") (name "Net-(U6A-RF2)") (class "Default")
      (node (ref "C17A") (pin "1") (pinfunction "1_1") (pintype "passive"))
      (node (ref "U6A") (pin "9") (pinfunction "RF2_9") (pintype "passive"))
    )
    (net (code "34") (name "Net-(U6A-RFC)") (class "Default")
      (node (ref "C22A") (pin "2") (pinfunction "2_2") (pintype "passive"))
      (node (ref "U6A") (pin "3") (pinfunction "RFC_3") (pintype "passive"))
    )
    (net (code "35") (name "Net-(U6B-RF1)") (class "Default")
      (node (ref "C21B") (pin "1") (pinfunction "1_1") (pintype "passive"))
      (node (ref "U6B") (pin "12") (pinfunction "RF1_12") (pintype "passive"))
    )
    (net (code "36") (name "Net-(U6B-RF2)") (class "Default")
      (node (ref "C17B") (pin "1") (pinfunction "1_1") (pintype "passive"))
      (node (ref "U6B") (pin "9") (pinfunction "RF2_9") (pintype "passive"))
    )
    (net (code "37") (name "Net-(U6B-RFC)") (class "Default")
      (node (ref "C22B") (pin "2") (pinfunction "2_2") (pintype "passive"))
      (node (ref "U6B") (pin "3") (pinfunction "RFC_3") (pintype "passive"))
    )
    (net (code "38") (name "unconnected-(CJ3A-Pad)") (class "Default")
      (node (ref "CJ3A") (pin "") (pintype "passive"))
    )
    (net (code "39") (name "unconnected-(CJ3B-Pad)") (class "Default")
      (node (ref "CJ3B") (pin "") (pintype "passive"))
    )
    (net (code "40") (name "unconnected-(CJ4A-Pad)") (class "Default")
      (node (ref "CJ4A") (pin "") (pintype "passive"))
    )
    (net (code "41") (name "unconnected-(CJ4B-Pad)") (class "Default")
      (node (ref "CJ4B") (pin "") (pintype "passive"))
    )
    (net (code "42") (name "unconnected-(CJ5A-Pad)") (class "Default")
      (node (ref "CJ5A") (pin "") (pintype "passive"))
    )
    (net (code "43") (name "unconnected-(CJ5B-Pad)") (class "Default")
      (node (ref "CJ5B") (pin "") (pintype "passive"))
    )
    (net (code "44") (name "unconnected-(CJ6A-Pad)") (class "Default")
      (node (ref "CJ6A") (pin "") (pintype "passive"))
    )
    (net (code "45") (name "unconnected-(CJ6B-Pad)") (class "Default")
      (node (ref "CJ6B") (pin "") (pintype "passive"))
    )
  )
)
